# 555.net
KiCad netlist of a schematic drawn in Altium Designer
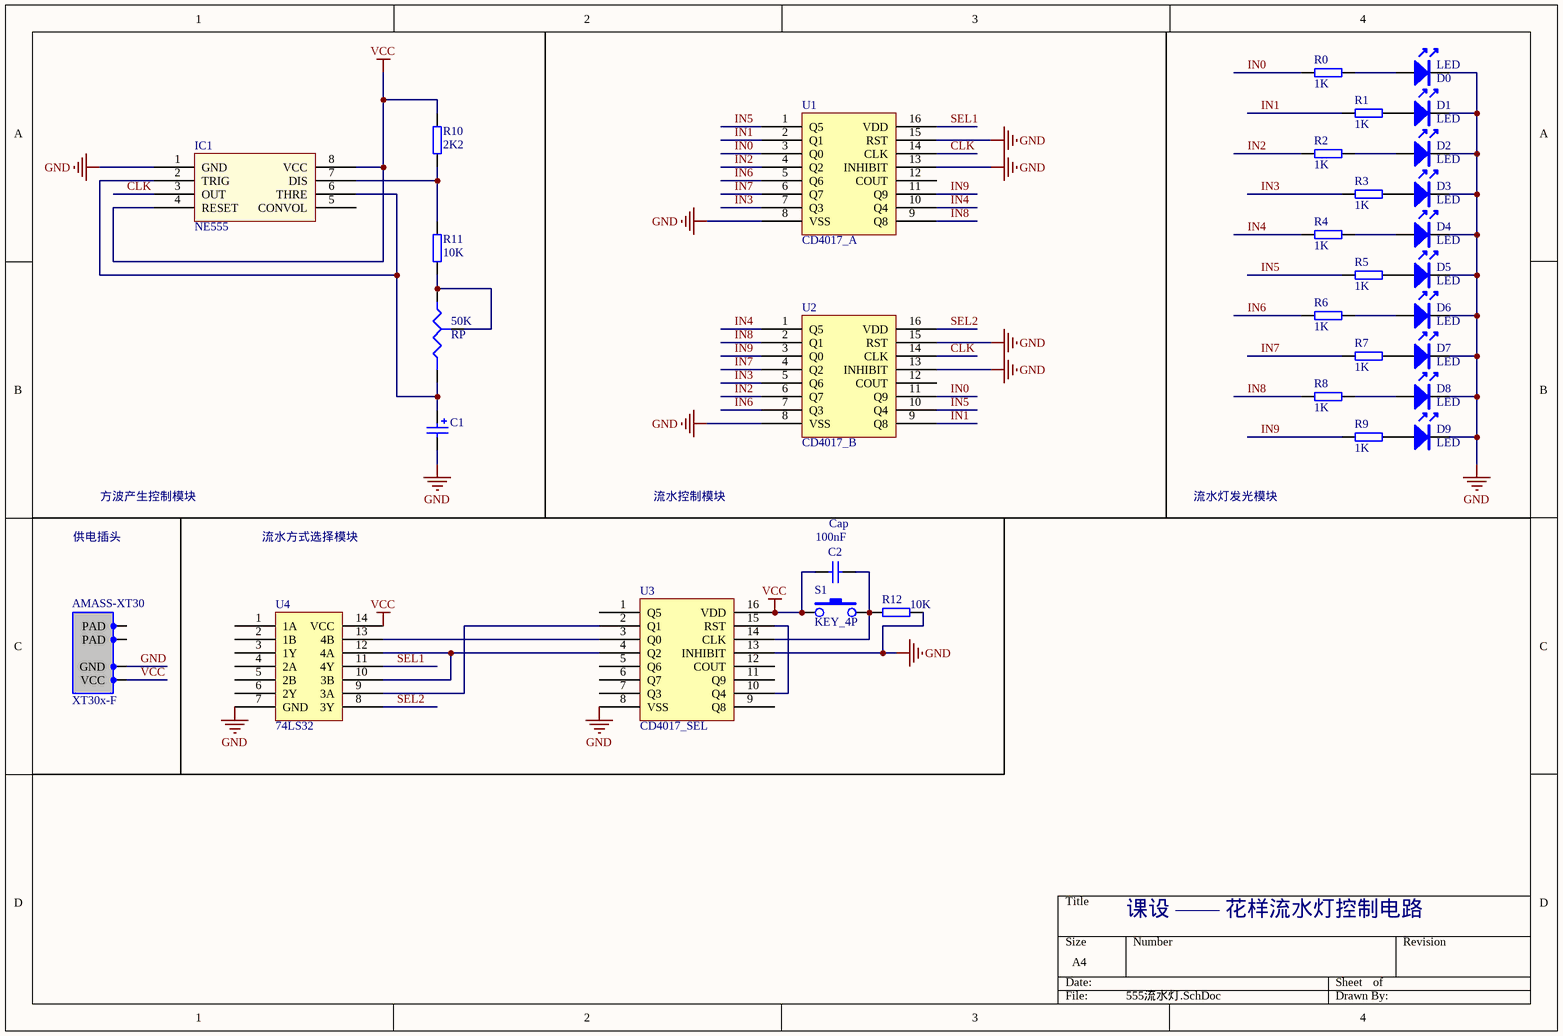
[diagram p0: 555流水灯.SchDoc]

(export (version "E")
  (design (tool "Eeschema 10.0.6"))
  (components
    (comp (ref "AMASS-XT30")
      (value "XT30x-F")
      (footprint "XT30U-M")
      (description "Amass防打火电源接口，XT30系列")
      (libsource (lib "14.17-Amass电源接口") (part "XT30"))
    )
    (comp (ref "C1")
      (value "1uF")
      (footprint "Component:RB3.5-7")
      (description "电解电容")
      (libsource (lib "Component") (part "Cap Pol1"))
    )
    (comp (ref "C2")
      (value "Cap")
      (footprint "RAD-0.3")
      (description "Capacitor")
      (fields (field (name "ALTIUM_VALUE") "100nF") (field (name "PUBLISHER") "Altium Limited"))
      (libsource (lib "Miscellaneous Devices") (part "Cap"))
    )
    (comp (ref "D0") (value "LED") (footprint "Component:LED_3MM") (libsource (lib "Component") (part "LED")))
    (comp (ref "D1") (value "LED") (footprint "Component:LED_3MM") (libsource (lib "Component") (part "LED")))
    (comp (ref "D2") (value "LED") (footprint "Component:LED_3MM") (libsource (lib "Component") (part "LED")))
    (comp (ref "D3") (value "LED") (footprint "Component:LED_3MM") (libsource (lib "Component") (part "LED")))
    (comp (ref "D4") (value "LED") (footprint "Component:LED_3MM") (libsource (lib "Component") (part "LED")))
    (comp (ref "D5") (value "LED") (footprint "Component:LED_3MM") (libsource (lib "Component") (part "LED")))
    (comp (ref "D6") (value "LED") (footprint "Component:LED_3MM") (libsource (lib "Component") (part "LED")))
    (comp (ref "D7") (value "LED") (footprint "Component:LED_3MM") (libsource (lib "Component") (part "LED")))
    (comp (ref "D8") (value "LED") (footprint "Component:LED_3MM") (libsource (lib "Component") (part "LED")))
    (comp (ref "D9") (value "LED") (footprint "Component:LED_3MM") (libsource (lib "Component") (part "LED")))
    (comp (ref "IC1")
      (value "NE555")
      (footprint "NE555P")
      (description "时基集成")
      (libsource (lib "Chip") (part "NE555"))
    )
    (comp (ref "R0")
      (value "1K")
      (footprint "Component:AXIAL-0.4")
      (description "电阻")
      (libsource (lib "Component") (part "RES1"))
    )
    (comp (ref "R1")
      (value "1K")
      (footprint "Component:AXIAL-0.4")
      (description "电阻")
      (libsource (lib "Component") (part "RES1"))
    )
    (comp (ref "R2")
      (value "1K")
      (footprint "Component:AXIAL-0.4")
      (description "电阻")
      (libsource (lib "Component") (part "RES1"))
    )
    (comp (ref "R3")
      (value "1K")
      (footprint "Component:AXIAL-0.4")
      (description "电阻")
      (libsource (lib "Component") (part "RES1"))
    )
    (comp (ref "R4")
      (value "1K")
      (footprint "Component:AXIAL-0.4")
      (description "电阻")
      (libsource (lib "Component") (part "RES1"))
    )
    (comp (ref "R5")
      (value "1K")
      (footprint "Component:AXIAL-0.4")
      (description "电阻")
      (libsource (lib "Component") (part "RES1"))
    )
    (comp (ref "R6")
      (value "1K")
      (footprint "Component:AXIAL-0.4")
      (description "电阻")
      (libsource (lib "Component") (part "RES1"))
    )
    (comp (ref "R7")
      (value "1K")
      (footprint "Component:AXIAL-0.4")
      (description "电阻")
      (libsource (lib "Component") (part "RES1"))
    )
    (comp (ref "R8")
      (value "1K")
      (footprint "Component:AXIAL-0.4")
      (description "电阻")
      (libsource (lib "Component") (part "RES1"))
    )
    (comp (ref "R9")
      (value "1K")
      (footprint "Component:AXIAL-0.4")
      (description "电阻")
      (libsource (lib "Component") (part "RES1"))
    )
    (comp (ref "R10")
      (value "2K2")
      (footprint "Component:AXIAL-0.4")
      (description "电阻")
      (libsource (lib "Component") (part "RES1"))
    )
    (comp (ref "R11")
      (value "10K")
      (footprint "Component:AXIAL-0.4")
      (description "电阻")
      (libsource (lib "Component") (part "RES1"))
    )
    (comp (ref "R12")
      (value "10K")
      (footprint "Component:AXIAL-0.4")
      (description "电阻")
      (libsource (lib "Component") (part "RES1"))
    )
    (comp (ref "RP")
      (value "50K")
      (footprint "Component:3296W")
      (description "可调电阻")
      (fields (field (name "PUBLISHER") "Altium Limited"))
      (libsource (lib "Component") (part "Res Tap"))
    )
    (comp (ref "S1")
      (value "KEY_4P")
      (footprint "Component:KEY_6*6")
      (description "轻触按键4P")
      (libsource (lib "Component") (part "KEY_4P"))
    )
    (comp (ref "U1") (value "CD4017_A") (footprint "CD4017") (libsource (lib "课设") (part "CD4017")))
    (comp (ref "U2") (value "CD4017_B") (footprint "CD4017") (libsource (lib "课设") (part "CD4017")))
    (comp (ref "U3") (value "CD4017_SEL") (footprint "CD4017") (libsource (lib "课设") (part "CD4017")))
    (comp (ref "U4") (value "74LS32") (footprint "74LS32") (libsource (lib "课设") (part "74LS32")))
  )
  (nets
    (net (code "1") (name "/CLK") (class "Default")
      (node (ref "IC1") (pin "3") (pinfunction "OUT_3") (pintype "passive"))
      (node (ref "U1") (pin "14") (pinfunction "CLK_14") (pintype "passive"))
      (node (ref "U2") (pin "14") (pinfunction "CLK_14") (pintype "passive"))
    )
    (net (code "2") (name "/IN0") (class "Default")
      (node (ref "R0") (pin "1") (pinfunction "1_1") (pintype "passive"))
      (node (ref "U1") (pin "3") (pinfunction "Q0_3") (pintype "passive"))
      (node (ref "U2") (pin "11") (pinfunction "Q9_11") (pintype "passive"))
    )
    (net (code "3") (name "/IN1") (class "Default")
      (node (ref "R1") (pin "1") (pinfunction "1_1") (pintype "passive"))
      (node (ref "U1") (pin "2") (pinfunction "Q1_2") (pintype "passive"))
      (node (ref "U2") (pin "9") (pinfunction "Q8_9") (pintype "passive"))
    )
    (net (code "4") (name "/IN2") (class "Default")
      (node (ref "R2") (pin "1") (pinfunction "1_1") (pintype "passive"))
      (node (ref "U1") (pin "4") (pinfunction "Q2_4") (pintype "passive"))
      (node (ref "U2") (pin "6") (pinfunction "Q7_6") (pintype "passive"))
    )
    (net (code "5") (name "/IN3") (class "Default")
      (node (ref "R3") (pin "1") (pinfunction "1_1") (pintype "passive"))
      (node (ref "U1") (pin "7") (pinfunction "Q3_7") (pintype "passive"))
      (node (ref "U2") (pin "5") (pinfunction "Q6_5") (pintype "passive"))
    )
    (net (code "6") (name "/IN4") (class "Default")
      (node (ref "R4") (pin "1") (pinfunction "1_1") (pintype "passive"))
      (node (ref "U1") (pin "10") (pinfunction "Q4_10") (pintype "passive"))
      (node (ref "U2") (pin "1") (pinfunction "Q5_1") (pintype "passive"))
    )
    (net (code "7") (name "/IN5") (class "Default")
      (node (ref "R5") (pin "1") (pinfunction "1_1") (pintype "passive"))
      (node (ref "U1") (pin "1") (pinfunction "Q5_1") (pintype "passive"))
      (node (ref "U2") (pin "10") (pinfunction "Q4_10") (pintype "passive"))
    )
    (net (code "8") (name "/IN6") (class "Default")
      (node (ref "R6") (pin "1") (pinfunction "1_1") (pintype "passive"))
      (node (ref "U1") (pin "5") (pinfunction "Q6_5") (pintype "passive"))
      (node (ref "U2") (pin "7") (pinfunction "Q3_7") (pintype "passive"))
    )
    (net (code "9") (name "/IN7") (class "Default")
      (node (ref "R7") (pin "1") (pinfunction "1_1") (pintype "passive"))
      (node (ref "U1") (pin "6") (pinfunction "Q7_6") (pintype "passive"))
      (node (ref "U2") (pin "4") (pinfunction "Q2_4") (pintype "passive"))
    )
    (net (code "10") (name "/IN8") (class "Default")
      (node (ref "R8") (pin "1") (pinfunction "1_1") (pintype "passive"))
      (node (ref "U1") (pin "9") (pinfunction "Q8_9") (pintype "passive"))
      (node (ref "U2") (pin "2") (pinfunction "Q1_2") (pintype "passive"))
    )
    (net (code "11") (name "/IN9") (class "Default")
      (node (ref "R9") (pin "1") (pinfunction "1_1") (pintype "passive"))
      (node (ref "U1") (pin "11") (pinfunction "Q9_11") (pintype "passive"))
      (node (ref "U2") (pin "3") (pinfunction "Q0_3") (pintype "passive"))
    )
    (net (code "12") (name "/SEL1") (class "Default")
      (node (ref "U1") (pin "16") (pinfunction "VDD_16") (pintype "passive"))
      (node (ref "U4") (pin "11") (pinfunction "4Y_11") (pintype "passive"))
    )
    (net (code "13") (name "/SEL2") (class "Default")
      (node (ref "U2") (pin "16") (pinfunction "VDD_16") (pintype "passive"))
      (node (ref "U4") (pin "8") (pinfunction "3Y_8") (pintype "passive"))
    )
    (net (code "14") (name "GND") (class "Default")
      (node (ref "AMASS-XT30") (pin "2") (pinfunction "GND_2") (pintype "passive"))
      (node (ref "C1") (pin "2") (pinfunction "2_2") (pintype "passive"))
      (node (ref "D0") (pin "2") (pinfunction "2_2") (pintype "passive"))
      (node (ref "D1") (pin "2") (pinfunction "2_2") (pintype "passive"))
      (node (ref "D2") (pin "2") (pinfunction "2_2") (pintype "passive"))
      (node (ref "D3") (pin "2") (pinfunction "2_2") (pintype "passive"))
      (node (ref "D4") (pin "2") (pinfunction "2_2") (pintype "passive"))
      (node (ref "D5") (pin "2") (pinfunction "2_2") (pintype "passive"))
      (node (ref "D6") (pin "2") (pinfunction "2_2") (pintype "passive"))
      (node (ref "D7") (pin "2") (pinfunction "2_2") (pintype "passive"))
      (node (ref "D8") (pin "2") (pinfunction "2_2") (pintype "passive"))
      (node (ref "D9") (pin "2") (pinfunction "2_2") (pintype "passive"))
      (node (ref "IC1") (pin "1") (pinfunction "GND_1") (pintype "passive"))
      (node (ref "R12") (pin "2") (pinfunction "2_2") (pintype "passive"))
      (node (ref "U1") (pin "13") (pinfunction "INHIBIT_13") (pintype "passive"))
      (node (ref "U1") (pin "15") (pinfunction "RST_15") (pintype "passive"))
      (node (ref "U1") (pin "8") (pinfunction "VSS_8") (pintype "passive"))
      (node (ref "U2") (pin "13") (pinfunction "INHIBIT_13") (pintype "passive"))
      (node (ref "U2") (pin "15") (pinfunction "RST_15") (pintype "passive"))
      (node (ref "U2") (pin "8") (pinfunction "VSS_8") (pintype "passive"))
      (node (ref "U3") (pin "13") (pinfunction "INHIBIT_13") (pintype "passive"))
      (node (ref "U3") (pin "8") (pinfunction "VSS_8") (pintype "passive"))
      (node (ref "U4") (pin "7") (pinfunction "GND_7") (pintype "passive"))
    )
    (net (code "15") (name "Net-(D0-Pad1)") (class "Default")
      (node (ref "D0") (pin "1") (pinfunction "1_1") (pintype "passive"))
      (node (ref "R0") (pin "2") (pinfunction "2_2") (pintype "passive"))
    )
    (net (code "16") (name "Net-(D1-Pad1)") (class "Default")
      (node (ref "D1") (pin "1") (pinfunction "1_1") (pintype "passive"))
      (node (ref "R1") (pin "2") (pinfunction "2_2") (pintype "passive"))
    )
    (net (code "17") (name "Net-(D2-Pad1)") (class "Default")
      (node (ref "D2") (pin "1") (pinfunction "1_1") (pintype "passive"))
      (node (ref "R2") (pin "2") (pinfunction "2_2") (pintype "passive"))
    )
    (net (code "18") (name "Net-(D3-Pad1)") (class "Default")
      (node (ref "D3") (pin "1") (pinfunction "1_1") (pintype "passive"))
      (node (ref "R3") (pin "2") (pinfunction "2_2") (pintype "passive"))
    )
    (net (code "19") (name "Net-(D4-Pad1)") (class "Default")
      (node (ref "D4") (pin "1") (pinfunction "1_1") (pintype "passive"))
      (node (ref "R4") (pin "2") (pinfunction "2_2") (pintype "passive"))
    )
    (net (code "20") (name "Net-(D5-Pad1)") (class "Default")
      (node (ref "D5") (pin "1") (pinfunction "1_1") (pintype "passive"))
      (node (ref "R5") (pin "2") (pinfunction "2_2") (pintype "passive"))
    )
    (net (code "21") (name "Net-(D6-Pad1)") (class "Default")
      (node (ref "D6") (pin "1") (pinfunction "1_1") (pintype "passive"))
      (node (ref "R6") (pin "2") (pinfunction "2_2") (pintype "passive"))
    )
    (net (code "22") (name "Net-(D7-Pad1)") (class "Default")
      (node (ref "D7") (pin "1") (pinfunction "1_1") (pintype "passive"))
      (node (ref "R7") (pin "2") (pinfunction "2_2") (pintype "passive"))
    )
    (net (code "23") (name "Net-(D8-Pad1)") (class "Default")
      (node (ref "D8") (pin "1") (pinfunction "1_1") (pintype "passive"))
      (node (ref "R8") (pin "2") (pinfunction "2_2") (pintype "passive"))
    )
    (net (code "24") (name "Net-(D9-Pad1)") (class "Default")
      (node (ref "D9") (pin "1") (pinfunction "1_1") (pintype "passive"))
      (node (ref "R9") (pin "2") (pinfunction "2_2") (pintype "passive"))
    )
    (net (code "25") (name "Net-(IC1-DIS)") (class "Default")
      (node (ref "IC1") (pin "7") (pinfunction "DIS_7") (pintype "passive"))
      (node (ref "R10") (pin "2") (pinfunction "2_2") (pintype "passive"))
      (node (ref "R11") (pin "1") (pinfunction "1_1") (pintype "passive"))
    )
    (net (code "26") (name "Net-(IC1-THRE)") (class "Default")
      (node (ref "C1") (pin "1") (pinfunction "1_1") (pintype "passive"))
      (node (ref "IC1") (pin "2") (pinfunction "TRIG_2") (pintype "passive"))
      (node (ref "IC1") (pin "6") (pinfunction "THRE_6") (pintype "passive"))
      (node (ref "RP") (pin "3") (pinfunction "B_3") (pintype "passive"))
    )
    (net (code "27") (name "Net-(RP-A)") (class "Default")
      (node (ref "R11") (pin "2") (pinfunction "2_2") (pintype "passive"))
      (node (ref "RP") (pin "1") (pinfunction "A_1") (pintype "passive"))
      (node (ref "RP") (pin "2") (pinfunction "TAP_2") (pintype "passive"))
    )
    (net (code "28") (name "Net-(U3-CLK)") (class "Default")
      (node (ref "C2") (pin "2") (pinfunction "2_2") (pintype "passive"))
      (node (ref "R12") (pin "1") (pinfunction "1_1") (pintype "passive"))
      (node (ref "S1") (pin "2") (pinfunction "2_2") (pintype "passive"))
      (node (ref "U3") (pin "14") (pinfunction "CLK_14") (pintype "passive"))
    )
    (net (code "29") (name "Net-(U3-Q0)") (class "Default")
      (node (ref "U3") (pin "3") (pinfunction "Q0_3") (pintype "passive"))
      (node (ref "U4") (pin "13") (pinfunction "4B_13") (pintype "passive"))
    )
    (net (code "30") (name "Net-(U3-Q1)") (class "Default")
      (node (ref "U3") (pin "2") (pinfunction "Q1_2") (pintype "passive"))
      (node (ref "U4") (pin "9") (pinfunction "3A_9") (pintype "passive"))
    )
    (net (code "31") (name "Net-(U3-Q2)") (class "Default")
      (node (ref "U3") (pin "4") (pinfunction "Q2_4") (pintype "passive"))
      (node (ref "U4") (pin "10") (pinfunction "3B_10") (pintype "passive"))
      (node (ref "U4") (pin "12") (pinfunction "4A_12") (pintype "passive"))
    )
    (net (code "32") (name "Net-(U3-Q4)") (class "Default")
      (node (ref "U3") (pin "10") (pinfunction "Q4_10") (pintype "passive"))
      (node (ref "U3") (pin "15") (pinfunction "RST_15") (pintype "passive"))
    )
    (net (code "33") (name "VCC") (class "Default")
      (node (ref "AMASS-XT30") (pin "1") (pinfunction "VCC_1") (pintype "passive"))
      (node (ref "C2") (pin "1") (pinfunction "1_1") (pintype "passive"))
      (node (ref "IC1") (pin "4") (pinfunction "RESET_4") (pintype "passive"))
      (node (ref "IC1") (pin "8") (pinfunction "VCC_8") (pintype "passive"))
      (node (ref "R10") (pin "1") (pinfunction "1_1") (pintype "passive"))
      (node (ref "S1") (pin "1") (pinfunction "1_1") (pintype "passive"))
      (node (ref "U3") (pin "16") (pinfunction "VDD_16") (pintype "passive"))
      (node (ref "U4") (pin "14") (pinfunction "VCC_14") (pintype "passive"))
    )
    (net (code "34") (name "unconnected-(AMASS-XT30-PAD-Pad0)") (class "Default")
      (node (ref "AMASS-XT30") (pin "0") (pinfunction "PAD_0") (pintype "passive"))
    )
    (net (code "35") (name "unconnected-(AMASS-XT30-PAD-Pad100)") (class "Default")
      (node (ref "AMASS-XT30") (pin "100") (pinfunction "PAD_100") (pintype "passive"))
    )
    (net (code "36") (name "unconnected-(IC1-CONVOL-Pad5)") (class "Default")
      (node (ref "IC1") (pin "5") (pinfunction "CONVOL_5") (pintype "passive"))
    )
    (net (code "37") (name "unconnected-(U1-COUT-Pad12)") (class "Default")
      (node (ref "U1") (pin "12") (pinfunction "COUT_12") (pintype "passive"))
    )
    (net (code "38") (name "unconnected-(U2-COUT-Pad12)") (class "Default")
      (node (ref "U2") (pin "12") (pinfunction "COUT_12") (pintype "passive"))
    )
    (net (code "39") (name "unconnected-(U3-COUT-Pad12)") (class "Default")
      (node (ref "U3") (pin "12") (pinfunction "COUT_12") (pintype "passive"))
    )
    (net (code "40") (name "unconnected-(U3-Q3-Pad7)") (class "Default")
      (node (ref "U3") (pin "7") (pinfunction "Q3_7") (pintype "passive"))
    )
    (net (code "41") (name "unconnected-(U3-Q5-Pad1)") (class "Default")
      (node (ref "U3") (pin "1") (pinfunction "Q5_1") (pintype "passive"))
    )
    (net (code "42") (name "unconnected-(U3-Q6-Pad5)") (class "Default")
      (node (ref "U3") (pin "5") (pinfunction "Q6_5") (pintype "passive"))
    )
    (net (code "43") (name "unconnected-(U3-Q7-Pad6)") (class "Default")
      (node (ref "U3") (pin "6") (pinfunction "Q7_6") (pintype "passive"))
    )
    (net (code "44") (name "unconnected-(U3-Q8-Pad9)") (class "Default")
      (node (ref "U3") (pin "9") (pinfunction "Q8_9") (pintype "passive"))
    )
    (net (code "45") (name "unconnected-(U3-Q9-Pad11)") (class "Default")
      (node (ref "U3") (pin "11") (pinfunction "Q9_11") (pintype "passive"))
    )
    (net (code "46") (name "unconnected-(U4-1A-Pad1)") (class "Default")
      (node (ref "U4") (pin "1") (pinfunction "1A_1") (pintype "passive"))
    )
    (net (code "47") (name "unconnected-(U4-1B-Pad2)") (class "Default")
      (node (ref "U4") (pin "2") (pinfunction "1B_2") (pintype "passive"))
    )
    (net (code "48") (name "unconnected-(U4-1Y-Pad3)") (class "Default")
      (node (ref "U4") (pin "3") (pinfunction "1Y_3") (pintype "passive"))
    )
    (net (code "49") (name "unconnected-(U4-2A-Pad4)") (class "Default")
      (node (ref "U4") (pin "4") (pinfunction "2A_4") (pintype "passive"))
    )
    (net (code "50") (name "unconnected-(U4-2B-Pad5)") (class "Default")
      (node (ref "U4") (pin "5") (pinfunction "2B_5") (pintype "passive"))
    )
    (net (code "51") (name "unconnected-(U4-2Y-Pad6)") (class "Default")
      (node (ref "U4") (pin "6") (pinfunction "2Y_6") (pintype "passive"))
    )
  )
)
